# 03_Power.net
KiCad netlist of a schematic drawn in Altium Designer
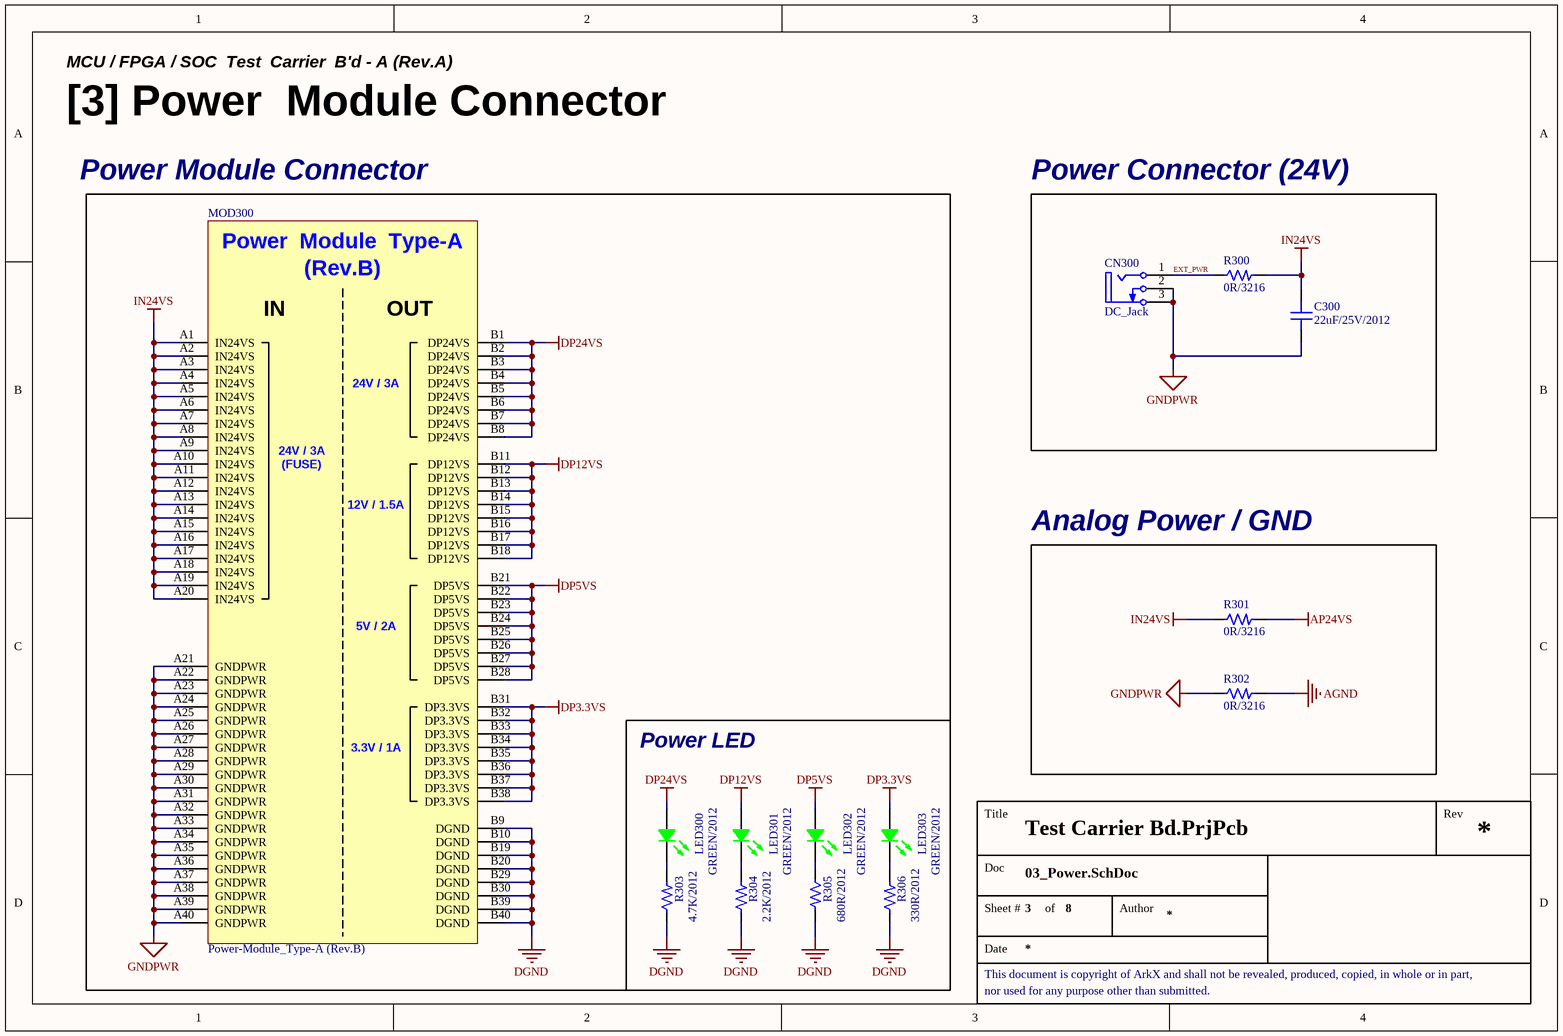
[diagram p0: 03_Power.SchDoc]

(export (version "E")
  (design (tool "Eeschema 10.0.6"))
  (components
    (comp (ref "C300")
      (value "22uF/25V/2012")
      (footprint "CAP 2012 (0805_INCH)")
      (description "Ceramic CAP_22uF/25V/2012")
      (fields (field (name "LCSC PART #") "C45783"))
      (libsource (lib "Arkx") (part "CAP_22uF/25V/2012"))
    )
    (comp (ref "CN300")
      (value "DC_Jack")
      (footprint "CON_DC-JACK")
      (libsource (lib "Arkx") (part "CON_DC-Jack"))
    )
    (comp (ref "LED300")
      (value "GREEN/2012")
      (footprint "LED MHT170RGBCT (GREEN)")
      (fields (field (name "LCSC PART #") "C2962094"))
      (libsource (lib "Arkx") (part "LED_MHT170RGBCT(GREEN)"))
    )
    (comp (ref "LED301")
      (value "GREEN/2012")
      (footprint "LED MHT170RGBCT (GREEN)")
      (fields (field (name "LCSC PART #") "C2962094"))
      (libsource (lib "Arkx") (part "LED_MHT170RGBCT(GREEN)"))
    )
    (comp (ref "LED302")
      (value "GREEN/2012")
      (footprint "LED MHT170RGBCT (GREEN)")
      (fields (field (name "LCSC PART #") "C2962094"))
      (libsource (lib "Arkx") (part "LED_MHT170RGBCT(GREEN)"))
    )
    (comp (ref "LED303")
      (value "GREEN/2012")
      (footprint "LED MHT170RGBCT (GREEN)")
      (fields (field (name "LCSC PART #") "C2962094"))
      (libsource (lib "Arkx") (part "LED_MHT170RGBCT(GREEN)"))
    )
    (comp (ref "MOD300")
      (value "Power-Module_Type-A (Rev.B)")
      (footprint "MOD_Power-Module_Type-A (Rev.B)")
      (description "Power-Module_(Type-A / Rev.B)")
      (libsource (lib "Arkx") (part "MOD_Power-Module_Type-A (Rev.B)"))
    )
    (comp (ref "R300")
      (value "0R/3216")
      (footprint "RES 3216 (1206_inch)")
      (description "RES_0R/3216/0.25W")
      (fields (field (name "LCSC PART #") "C17888"))
      (libsource (lib "Arkx") (part "RES_0R/3216/0.25W"))
    )
    (comp (ref "R301")
      (value "0R/3216")
      (footprint "RES 3216 (1206_inch)")
      (description "RES_0R/3216/0.25W")
      (fields (field (name "LCSC PART #") "C17888"))
      (libsource (lib "Arkx") (part "RES_0R/3216/0.25W"))
    )
    (comp (ref "R302")
      (value "0R/3216")
      (footprint "RES 3216 (1206_inch)")
      (description "RES_0R/3216/0.25W")
      (fields (field (name "LCSC PART #") "C17888"))
      (libsource (lib "Arkx") (part "RES_0R/3216/0.25W"))
    )
    (comp (ref "R303")
      (value "4.7K/2012")
      (footprint "RES 2012 (0805_inch)")
      (description "RES_4.7K/2012/0.125W")
      (fields (field (name "LCSC PART #") "C17673"))
      (libsource (lib "Arkx") (part "RES_4.7K/2012/0.125W"))
    )
    (comp (ref "R304")
      (value "2.2K/2012")
      (footprint "RES 2012 (0805_inch)")
      (description "RES_2.2K/2012/0.125W")
      (fields (field (name "LCSC PART #") "C17520"))
      (libsource (lib "Arkx") (part "RES_2.2K/2012/0.125W"))
    )
    (comp (ref "R305")
      (value "680R/2012")
      (footprint "RES 2012 (0805_inch)")
      (description "RES_680R/2012/0.125W")
      (fields (field (name "LCSC PART #") "C17798"))
      (libsource (lib "Arkx") (part "RES_680R/2012/0.125W"))
    )
    (comp (ref "R306")
      (value "330R/2012")
      (footprint "RES 2012 (0805_inch)")
      (description "RES_330R/2012/0.125W")
      (fields (field (name "LCSC PART #") "C17630"))
      (libsource (lib "Arkx") (part "RES_330R/2012/0.125W"))
    )
  )
  (nets
    (net (code "1") (name "/EXT_PWR") (class "Default")
      (node (ref "CN300") (pin "1") (pinfunction "VCC_1") (pintype "power_in"))
      (node (ref "R300") (pin "1") (pinfunction "1_1") (pintype "passive"))
    )
    (net (code "2") (name "AGND") (class "Default")
      (node (ref "R302") (pin "2") (pinfunction "2_2") (pintype "passive"))
    )
    (net (code "3") (name "AP24VS") (class "Default")
      (node (ref "R301") (pin "2") (pinfunction "2_2") (pintype "passive"))
    )
    (net (code "4") (name "DGND") (class "Default")
      (node (ref "MOD300") (pin "B10") (pinfunction "DGND_B10") (pintype "passive"))
      (node (ref "MOD300") (pin "B19") (pinfunction "DGND_B19") (pintype "passive"))
      (node (ref "MOD300") (pin "B20") (pinfunction "DGND_B20") (pintype "passive"))
      (node (ref "MOD300") (pin "B29") (pinfunction "DGND_B29") (pintype "passive"))
      (node (ref "MOD300") (pin "B30") (pinfunction "DGND_B30") (pintype "passive"))
      (node (ref "MOD300") (pin "B39") (pinfunction "DGND_B39") (pintype "passive"))
      (node (ref "MOD300") (pin "B40") (pinfunction "DGND_B40") (pintype "passive"))
      (node (ref "MOD300") (pin "B9") (pinfunction "DGND_B9") (pintype "passive"))
      (node (ref "R303") (pin "1") (pinfunction "1_1") (pintype "passive"))
      (node (ref "R304") (pin "1") (pinfunction "1_1") (pintype "passive"))
      (node (ref "R305") (pin "2") (pinfunction "2_2") (pintype "passive"))
      (node (ref "R306") (pin "1") (pinfunction "1_1") (pintype "passive"))
    )
    (net (code "5") (name "DP3.3VS") (class "Default")
      (node (ref "LED303") (pin "4") (pinfunction "Common_Anode_4") (pintype "passive"))
      (node (ref "MOD300") (pin "B31") (pinfunction "DP3.3VS_B31") (pintype "passive"))
      (node (ref "MOD300") (pin "B32") (pinfunction "DP3.3VS_B32") (pintype "passive"))
      (node (ref "MOD300") (pin "B33") (pinfunction "DP3.3VS_B33") (pintype "passive"))
      (node (ref "MOD300") (pin "B34") (pinfunction "DP3.3VS_B34") (pintype "passive"))
      (node (ref "MOD300") (pin "B35") (pinfunction "DP3.3VS_B35") (pintype "passive"))
      (node (ref "MOD300") (pin "B36") (pinfunction "DP3.3VS_B36") (pintype "passive"))
      (node (ref "MOD300") (pin "B37") (pinfunction "DP3.3VS_B37") (pintype "passive"))
      (node (ref "MOD300") (pin "B38") (pinfunction "DP3.3VS_B38") (pintype "passive"))
    )
    (net (code "6") (name "DP5VS") (class "Default")
      (node (ref "LED302") (pin "4") (pinfunction "Common_Anode_4") (pintype "passive"))
      (node (ref "MOD300") (pin "B21") (pinfunction "DP5VS_B21") (pintype "passive"))
      (node (ref "MOD300") (pin "B22") (pinfunction "DP5VS_B22") (pintype "passive"))
      (node (ref "MOD300") (pin "B23") (pinfunction "DP5VS_B23") (pintype "passive"))
      (node (ref "MOD300") (pin "B24") (pinfunction "DP5VS_B24") (pintype "passive"))
      (node (ref "MOD300") (pin "B25") (pinfunction "DP5VS_B25") (pintype "passive"))
      (node (ref "MOD300") (pin "B26") (pinfunction "DP5VS_B26") (pintype "passive"))
      (node (ref "MOD300") (pin "B27") (pinfunction "DP5VS_B27") (pintype "passive"))
      (node (ref "MOD300") (pin "B28") (pinfunction "DP5VS_B28") (pintype "passive"))
    )
    (net (code "7") (name "DP12VS") (class "Default")
      (node (ref "LED301") (pin "4") (pinfunction "Common_Anode_4") (pintype "passive"))
      (node (ref "MOD300") (pin "B11") (pinfunction "DP12VS_B11") (pintype "passive"))
      (node (ref "MOD300") (pin "B12") (pinfunction "DP12VS_B12") (pintype "passive"))
      (node (ref "MOD300") (pin "B13") (pinfunction "DP12VS_B13") (pintype "passive"))
      (node (ref "MOD300") (pin "B14") (pinfunction "DP12VS_B14") (pintype "passive"))
      (node (ref "MOD300") (pin "B15") (pinfunction "DP12VS_B15") (pintype "passive"))
      (node (ref "MOD300") (pin "B16") (pinfunction "DP12VS_B16") (pintype "passive"))
      (node (ref "MOD300") (pin "B17") (pinfunction "DP12VS_B17") (pintype "passive"))
      (node (ref "MOD300") (pin "B18") (pinfunction "DP12VS_B18") (pintype "passive"))
    )
    (net (code "8") (name "DP24VS") (class "Default")
      (node (ref "LED300") (pin "4") (pinfunction "Common_Anode_4") (pintype "passive"))
      (node (ref "MOD300") (pin "B1") (pinfunction "DP24VS_B1") (pintype "passive"))
      (node (ref "MOD300") (pin "B2") (pinfunction "DP24VS_B2") (pintype "passive"))
      (node (ref "MOD300") (pin "B3") (pinfunction "DP24VS_B3") (pintype "passive"))
      (node (ref "MOD300") (pin "B4") (pinfunction "DP24VS_B4") (pintype "passive"))
      (node (ref "MOD300") (pin "B5") (pinfunction "DP24VS_B5") (pintype "passive"))
      (node (ref "MOD300") (pin "B6") (pinfunction "DP24VS_B6") (pintype "passive"))
      (node (ref "MOD300") (pin "B7") (pinfunction "DP24VS_B7") (pintype "passive"))
      (node (ref "MOD300") (pin "B8") (pinfunction "DP24VS_B8") (pintype "passive"))
    )
    (net (code "9") (name "GNDPWR") (class "Default")
      (node (ref "C300") (pin "2") (pinfunction "2_2") (pintype "passive"))
      (node (ref "CN300") (pin "2") (pinfunction "GND_2") (pintype "power_in"))
      (node (ref "CN300") (pin "3") (pinfunction "GND_3") (pintype "power_in"))
      (node (ref "MOD300") (pin "A21") (pinfunction "GNDPWR_A21") (pintype "passive"))
      (node (ref "MOD300") (pin "A22") (pinfunction "GNDPWR_A22") (pintype "passive"))
      (node (ref "MOD300") (pin "A23") (pinfunction "GNDPWR_A23") (pintype "passive"))
      (node (ref "MOD300") (pin "A24") (pinfunction "GNDPWR_A24") (pintype "passive"))
      (node (ref "MOD300") (pin "A25") (pinfunction "GNDPWR_A25") (pintype "passive"))
      (node (ref "MOD300") (pin "A26") (pinfunction "GNDPWR_A26") (pintype "passive"))
      (node (ref "MOD300") (pin "A27") (pinfunction "GNDPWR_A27") (pintype "passive"))
      (node (ref "MOD300") (pin "A28") (pinfunction "GNDPWR_A28") (pintype "passive"))
      (node (ref "MOD300") (pin "A29") (pinfunction "GNDPWR_A29") (pintype "passive"))
      (node (ref "MOD300") (pin "A30") (pinfunction "GNDPWR_A30") (pintype "passive"))
      (node (ref "MOD300") (pin "A31") (pinfunction "GNDPWR_A31") (pintype "passive"))
      (node (ref "MOD300") (pin "A32") (pinfunction "GNDPWR_A32") (pintype "passive"))
      (node (ref "MOD300") (pin "A33") (pinfunction "GNDPWR_A33") (pintype "passive"))
      (node (ref "MOD300") (pin "A34") (pinfunction "GNDPWR_A34") (pintype "passive"))
      (node (ref "MOD300") (pin "A35") (pinfunction "GNDPWR_A35") (pintype "passive"))
      (node (ref "MOD300") (pin "A36") (pinfunction "GNDPWR_A36") (pintype "passive"))
      (node (ref "MOD300") (pin "A37") (pinfunction "GNDPWR_A37") (pintype "passive"))
      (node (ref "MOD300") (pin "A38") (pinfunction "GNDPWR_A38") (pintype "passive"))
      (node (ref "MOD300") (pin "A39") (pinfunction "GNDPWR_A39") (pintype "passive"))
      (node (ref "MOD300") (pin "A40") (pinfunction "GNDPWR_A40") (pintype "passive"))
      (node (ref "R302") (pin "1") (pinfunction "1_1") (pintype "passive"))
    )
    (net (code "10") (name "IN24VS") (class "Default")
      (node (ref "C300") (pin "1") (pinfunction "1_1") (pintype "passive"))
      (node (ref "MOD300") (pin "A1") (pinfunction "IN24VS_A1") (pintype "passive"))
      (node (ref "MOD300") (pin "A10") (pinfunction "IN24VS_A10") (pintype "passive"))
      (node (ref "MOD300") (pin "A11") (pinfunction "IN24VS_A11") (pintype "passive"))
      (node (ref "MOD300") (pin "A12") (pinfunction "IN24VS_A12") (pintype "passive"))
      (node (ref "MOD300") (pin "A13") (pinfunction "IN24VS_A13") (pintype "passive"))
      (node (ref "MOD300") (pin "A14") (pinfunction "IN24VS_A14") (pintype "passive"))
      (node (ref "MOD300") (pin "A15") (pinfunction "IN24VS_A15") (pintype "passive"))
      (node (ref "MOD300") (pin "A16") (pinfunction "IN24VS_A16") (pintype "passive"))
      (node (ref "MOD300") (pin "A17") (pinfunction "IN24VS_A17") (pintype "passive"))
      (node (ref "MOD300") (pin "A18") (pinfunction "IN24VS_A18") (pintype "passive"))
      (node (ref "MOD300") (pin "A19") (pinfunction "IN24VS_A19") (pintype "passive"))
      (node (ref "MOD300") (pin "A2") (pinfunction "IN24VS_A2") (pintype "passive"))
      (node (ref "MOD300") (pin "A20") (pinfunction "IN24VS_A20") (pintype "passive"))
      (node (ref "MOD300") (pin "A3") (pinfunction "IN24VS_A3") (pintype "passive"))
      (node (ref "MOD300") (pin "A4") (pinfunction "IN24VS_A4") (pintype "passive"))
      (node (ref "MOD300") (pin "A5") (pinfunction "IN24VS_A5") (pintype "passive"))
      (node (ref "MOD300") (pin "A6") (pinfunction "IN24VS_A6") (pintype "passive"))
      (node (ref "MOD300") (pin "A7") (pinfunction "IN24VS_A7") (pintype "passive"))
      (node (ref "MOD300") (pin "A8") (pinfunction "IN24VS_A8") (pintype "passive"))
      (node (ref "MOD300") (pin "A9") (pinfunction "IN24VS_A9") (pintype "passive"))
      (node (ref "R300") (pin "2") (pinfunction "2_2") (pintype "passive"))
      (node (ref "R301") (pin "1") (pinfunction "1_1") (pintype "passive"))
    )
    (net (code "11") (name "Net-(LED300-GREEN)") (class "Default")
      (node (ref "LED300") (pin "2") (pinfunction "GREEN_2") (pintype "passive"))
      (node (ref "R303") (pin "2") (pinfunction "2_2") (pintype "passive"))
    )
    (net (code "12") (name "Net-(LED301-GREEN)") (class "Default")
      (node (ref "LED301") (pin "2") (pinfunction "GREEN_2") (pintype "passive"))
      (node (ref "R304") (pin "2") (pinfunction "2_2") (pintype "passive"))
    )
    (net (code "13") (name "Net-(LED302-GREEN)") (class "Default")
      (node (ref "LED302") (pin "2") (pinfunction "GREEN_2") (pintype "passive"))
      (node (ref "R305") (pin "1") (pinfunction "1_1") (pintype "passive"))
    )
    (net (code "14") (name "Net-(LED303-GREEN)") (class "Default")
      (node (ref "LED303") (pin "2") (pinfunction "GREEN_2") (pintype "passive"))
      (node (ref "R306") (pin "2") (pinfunction "2_2") (pintype "passive"))
    )
  )
)
